# LB_BIT_o6_BUZZER-v03_3_3.net
KiCad netlist of a schematic drawn in EAGLE
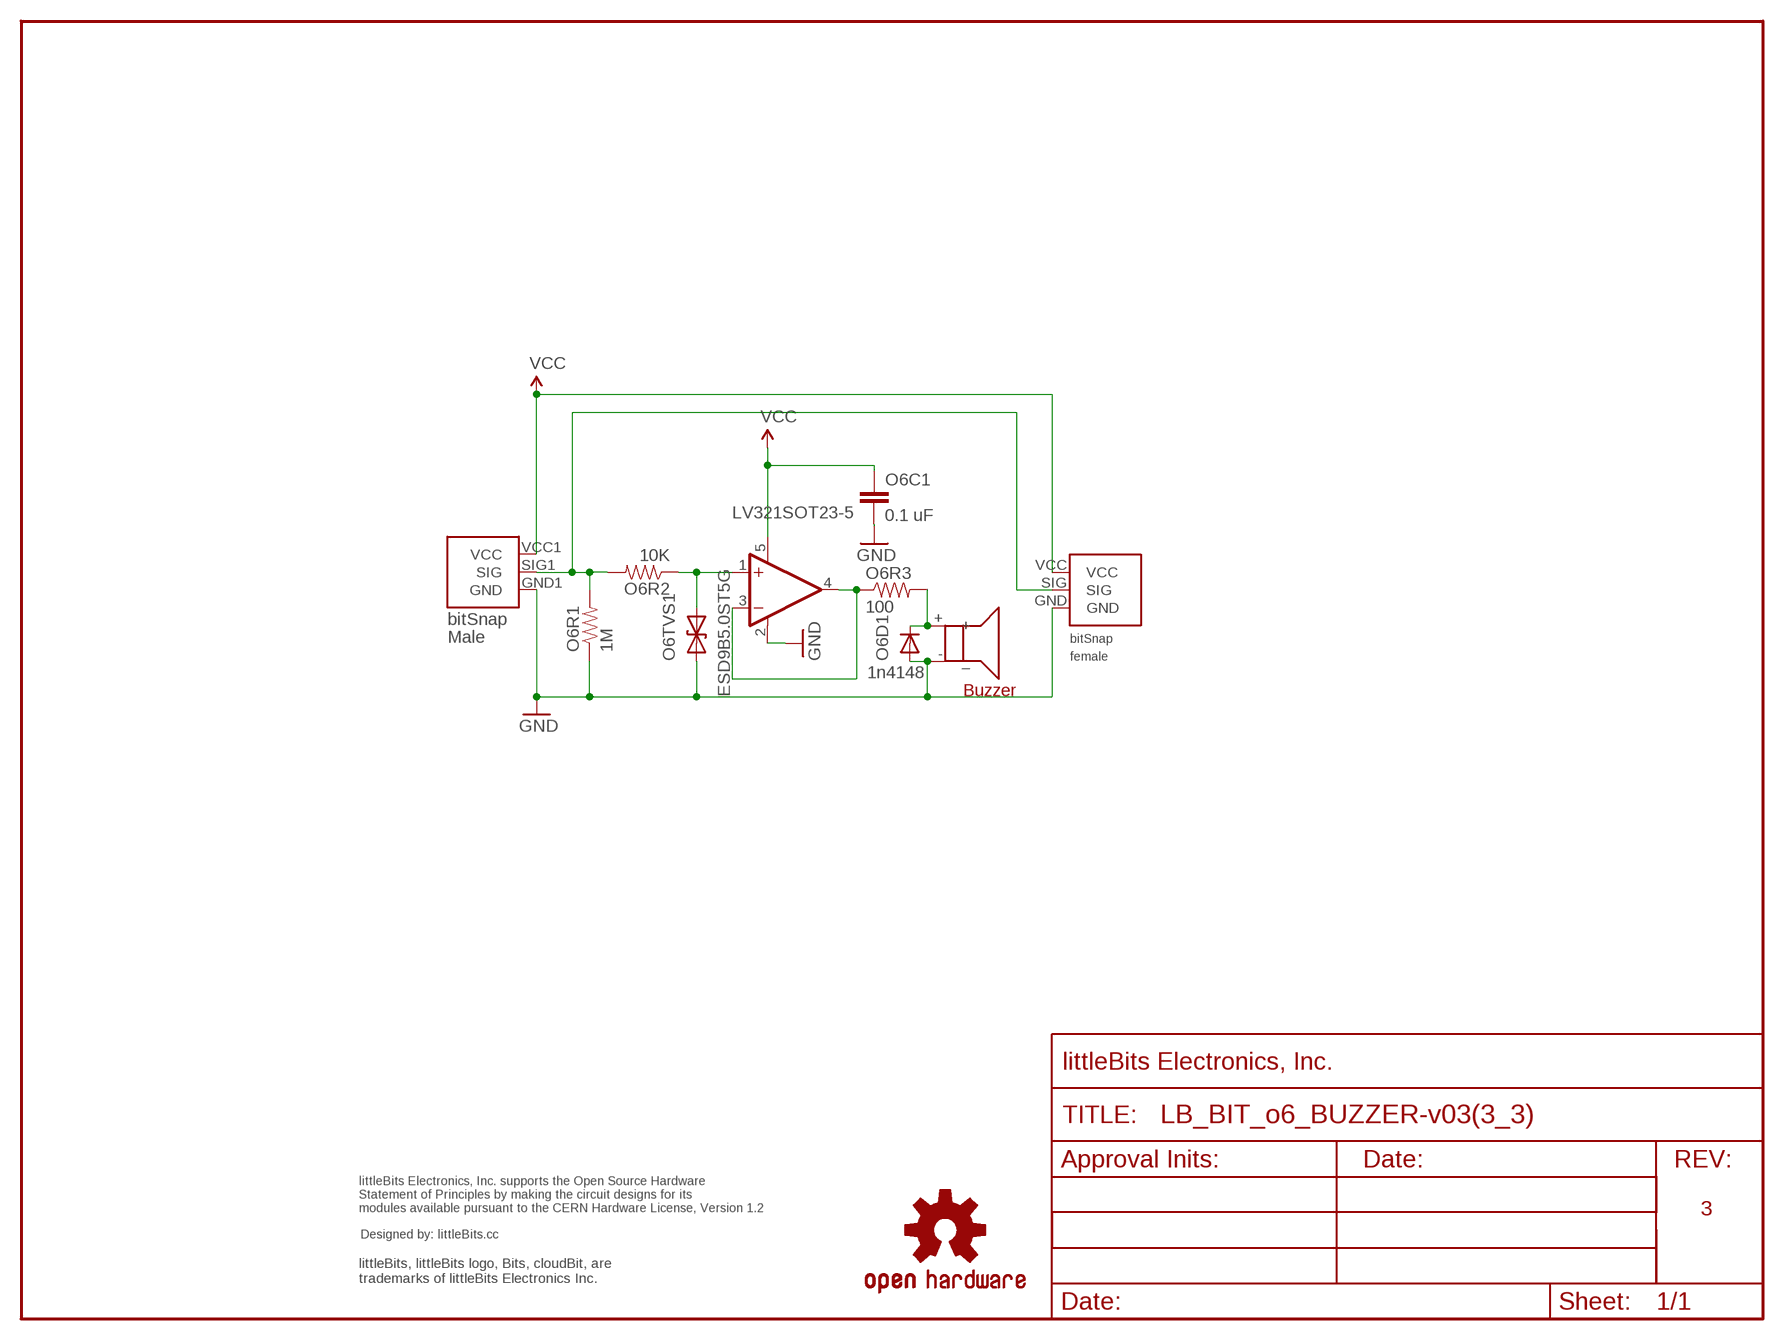
[diagram p0: schematic, sheet 1]

(export (version "E")
  (design (tool "Eeschema 10.0.6"))
  (components
    (comp (ref "O6BSF1")
      (value "BITSNAP_V03_FEMALE")
      (footprint "eagle-import:BITSNAP_V03_FEMALE")
      (libsource (lib "eagle-import") (part "BITSNAP_V03_FEMALE"))
    )
    (comp (ref "O6BSM1")
      (value "BITSNAP_V03_MALE")
      (footprint "eagle-import:BITSNAP_V03_MALE")
      (libsource (lib "eagle-import") (part "BITSNAP_V03_MALE"))
    )
    (comp (ref "O6C1")
      (value "0.1 uF")
      (footprint "eagle-import:CAP-0603")
      (libsource (lib "eagle-import") (part "CAPCAP-0603"))
    )
    (comp (ref "O6D1")
      (value "1n4148")
      (footprint "eagle-import:SOD-323")
      (libsource (lib "eagle-import") (part "DIODESOD"))
    )
    (comp (ref "O6R1")
      (value "1M")
      (footprint "eagle-import:RES-0603")
      (libsource (lib "eagle-import") (part "RESISTOR0603"))
    )
    (comp (ref "O6R2")
      (value "10K")
      (footprint "eagle-import:RES-0603")
      (libsource (lib "eagle-import") (part "RESISTOR0603"))
    )
    (comp (ref "O6R3")
      (value "100")
      (footprint "eagle-import:RES-0603")
      (libsource (lib "eagle-import") (part "RESISTOR0603"))
    )
    (comp (ref "O6TVS1")
      (value "ESD9B5.0ST5G")
      (footprint "eagle-import:SOD-923")
      (libsource (lib "eagle-import") (part "DIODE-TVSSOD-923"))
    )
    (comp (ref "O6U1")
      (value "LV321SOT23-5")
      (footprint "eagle-import:SOT23-5")
      (libsource (lib "eagle-import") (part "LV321SOT23-5"))
    )
    (comp (ref "O6U2")
      (value "BUZZER-JSH2317AT")
      (footprint "eagle-import:BUZZER-JSH2317AT")
      (libsource (lib "eagle-import") (part "BUZZER-JSH2317AT"))
    )
    (comp (ref "U$1")
      (value "FRAME-LETTER-OHWOHW")
      (footprint "eagle-import:FABDWG01-OHW")
      (libsource (lib "eagle-import") (part "FRAME-LETTER-OHWOHW"))
    )
    (comp (ref "U$2")
      (value "OSHWCREDIT")
      (footprint "eagle-import:OSHWCREDIT")
      (libsource (lib "eagle-import") (part "OSHWCREDIT"))
    )
    (comp (ref "U$16")
      (value "OSHW-LOGOL")
      (footprint "eagle-import:OSHW-LOGO-L")
      (libsource (lib "eagle-import") (part "OSHW-LOGOL"))
    )
  )
  (nets
    (net (code "1") (name "GND") (class "Default")
      (node (ref "O6BSF1") (pin "GND") (pinfunction "GND_GND") (pintype "bidirectional"))
      (node (ref "O6BSM1") (pin "GND1") (pinfunction "GND_GND1") (pintype "bidirectional"))
      (node (ref "O6C1") (pin "2") (pinfunction "2_2") (pintype "passive"))
      (node (ref "O6D1") (pin "2") (pinfunction "A_2") (pintype "passive"))
      (node (ref "O6R1") (pin "1") (pinfunction "1_1") (pintype "passive"))
      (node (ref "O6TVS1") (pin "1") (pinfunction "A_1") (pintype "passive"))
      (node (ref "O6U1") (pin "2") (pinfunction "V-_2") (pintype "power_in"))
      (node (ref "O6U2") (pin "-") (pinfunction "__-") (pintype "bidirectional"))
    )
    (net (code "2") (name "Net-(O6BSM1-SIG)") (class "Default")
      (node (ref "O6BSF1") (pin "SIG") (pinfunction "SIG_SIG") (pintype "bidirectional"))
      (node (ref "O6BSM1") (pin "SIG1") (pinfunction "SIG_SIG1") (pintype "bidirectional"))
      (node (ref "O6R1") (pin "2") (pinfunction "2_2") (pintype "passive"))
      (node (ref "O6R2") (pin "2") (pinfunction "2_2") (pintype "passive"))
    )
    (net (code "3") (name "Net-(O6D1-C)") (class "Default")
      (node (ref "O6D1") (pin "1") (pinfunction "C_1") (pintype "passive"))
      (node (ref "O6R3") (pin "2") (pinfunction "2_2") (pintype "passive"))
      (node (ref "O6U2") (pin "+") (pinfunction "+_+") (pintype "bidirectional"))
    )
    (net (code "4") (name "Net-(O6TVS1-C)") (class "Default")
      (node (ref "O6R2") (pin "1") (pinfunction "1_1") (pintype "passive"))
      (node (ref "O6TVS1") (pin "2") (pinfunction "C_2") (pintype "passive"))
      (node (ref "O6U1") (pin "1") (pinfunction "+IN_1") (pintype "input"))
    )
    (net (code "5") (name "Net-(O6U1--IN)") (class "Default")
      (node (ref "O6R3") (pin "1") (pinfunction "1_1") (pintype "passive"))
      (node (ref "O6U1") (pin "3") (pinfunction "-IN_3") (pintype "input"))
      (node (ref "O6U1") (pin "4") (pinfunction "OUT_4") (pintype "output"))
    )
    (net (code "6") (name "VCC") (class "Default")
      (node (ref "O6BSF1") (pin "VCC") (pinfunction "VCC_VCC") (pintype "bidirectional"))
      (node (ref "O6BSM1") (pin "VCC1") (pinfunction "VCC_VCC1") (pintype "bidirectional"))
      (node (ref "O6C1") (pin "1") (pinfunction "1_1") (pintype "passive"))
      (node (ref "O6U1") (pin "5") (pinfunction "V+_5") (pintype "power_in"))
    )
  )
)
